# InterfaceGSM.net
KiCad netlist of a schematic drawn in Altium Designer
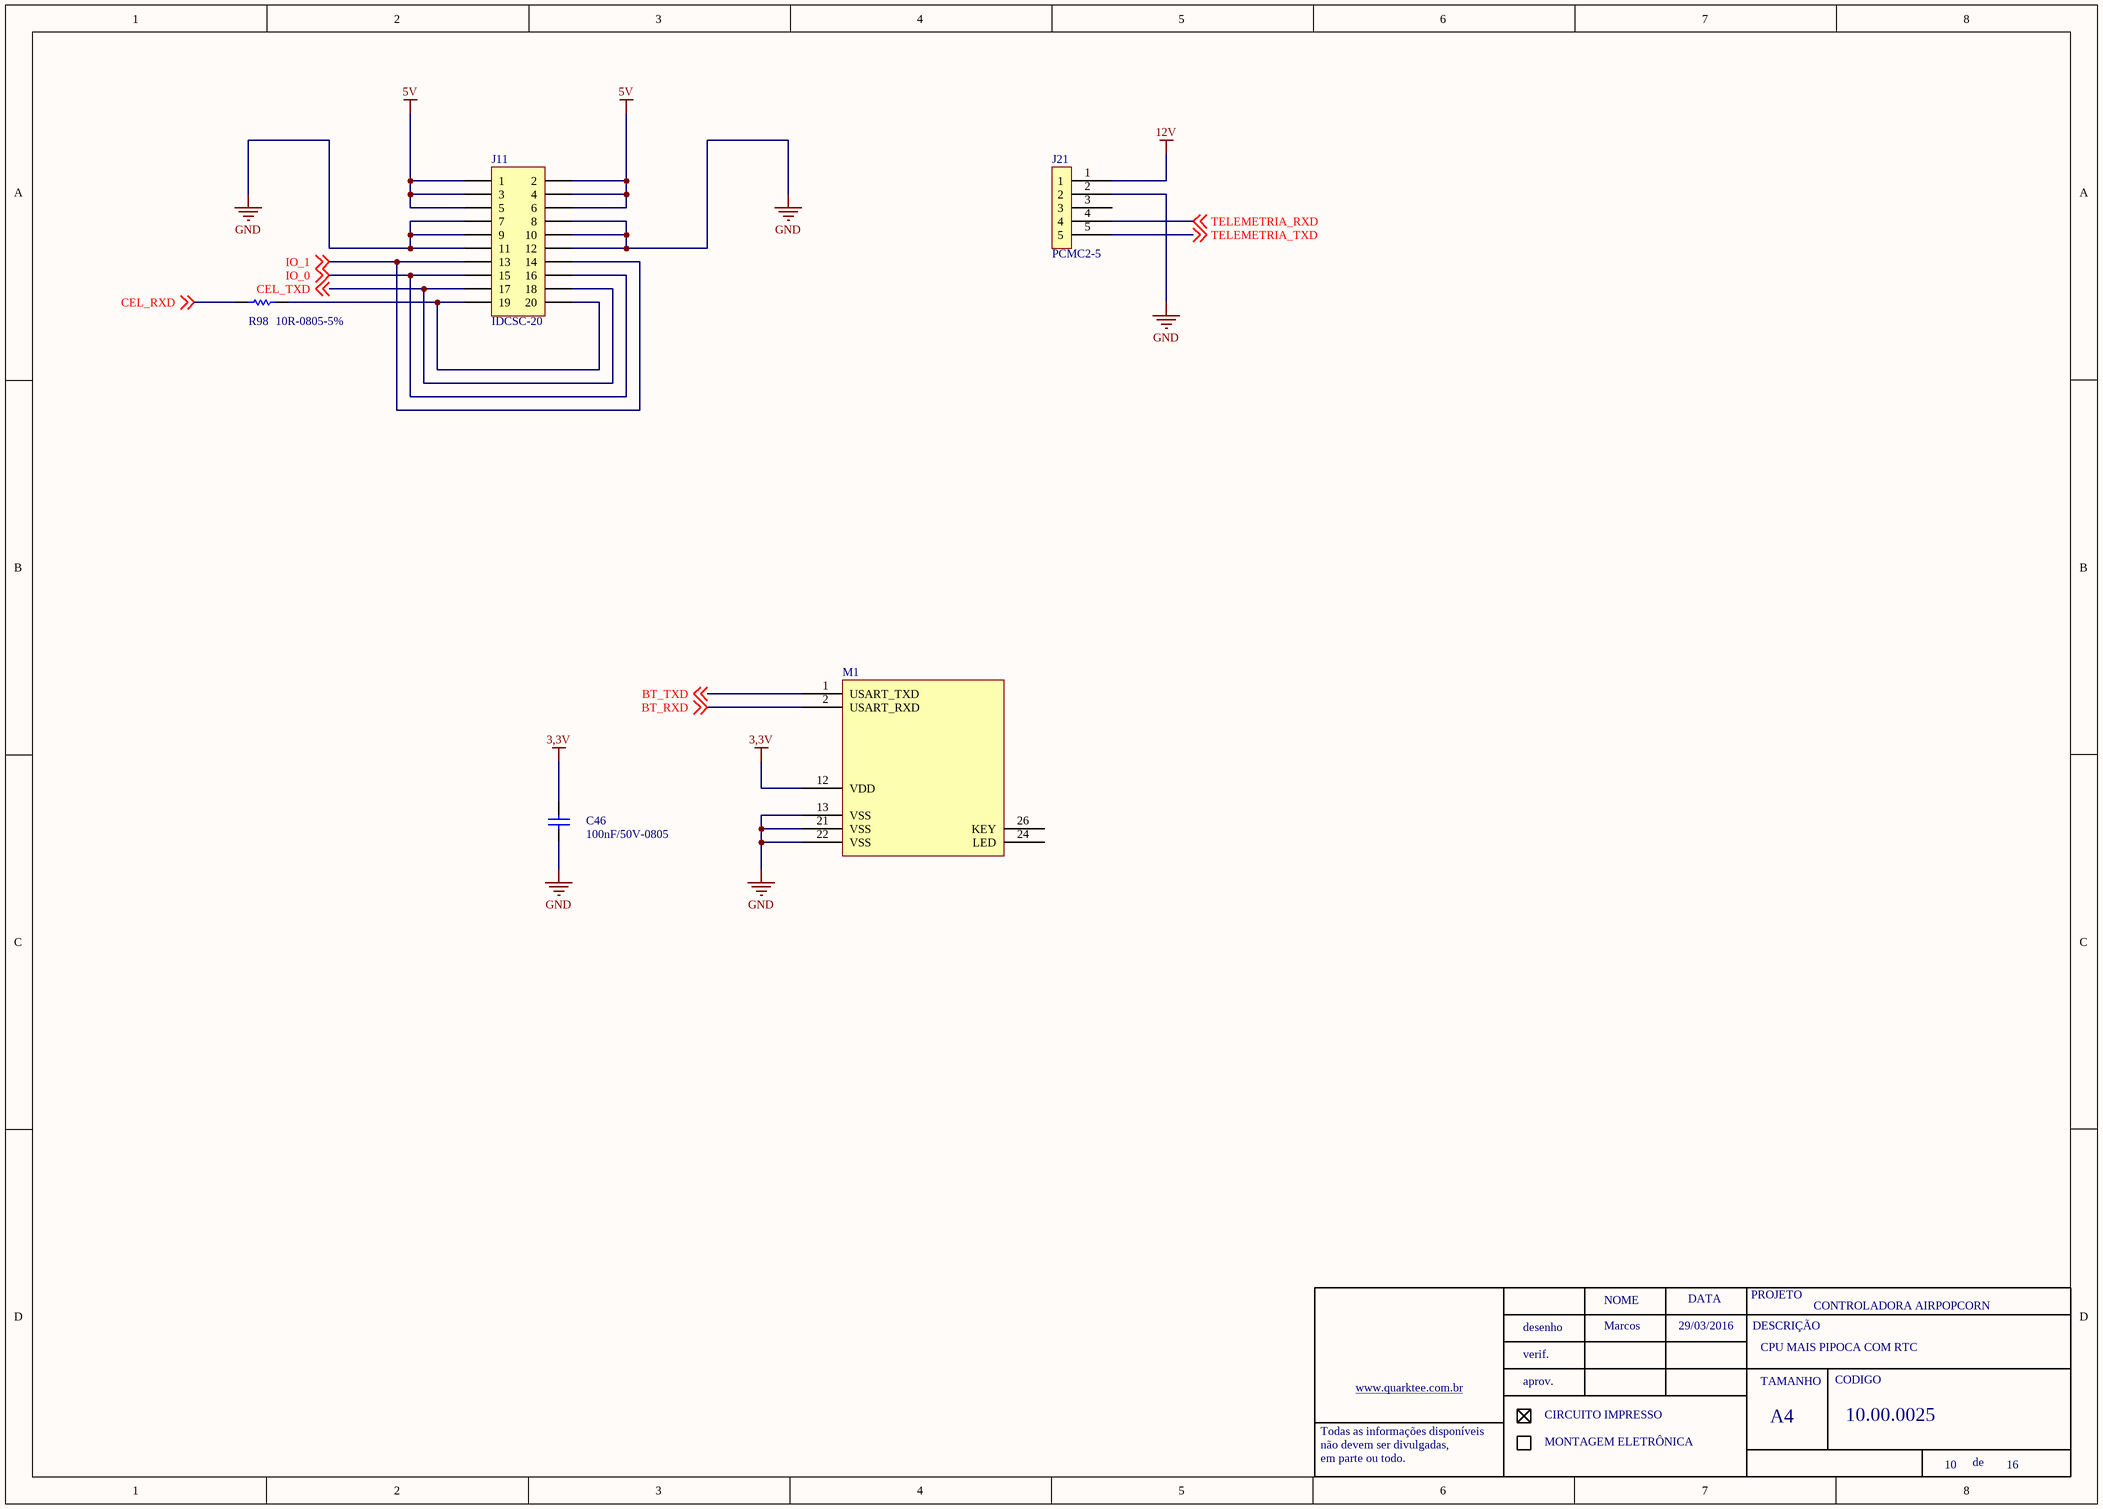
[diagram p0: InterfaceGSM.SchDoc]

(export (version "E")
  (design (tool "Eeschema 10.0.6"))
  (components
    (comp (ref "C46")
      (value "100nF/50V-0805")
      (footprint "0805-REVISADO O")
      (description "100nF/50-0805-NPO")
      (libsource (lib "AquinoLib") (part "100nF/50-0805-NPO"))
    )
    (comp (ref "J11")
      (value "IDCSC-20")
      (footprint "IDCSC-20")
      (libsource (lib "ChaveDigital3") (part "IDC 10x2"))
    )
    (comp (ref "J21") (value "PCMC2-5") (footprint "PCMC2-5") (libsource (lib "AquinoLib") (part "PCMC2-5")))
    (comp (ref "M1") (value "~") (description "HC-06") (libsource (lib "AquinoLib") (part "HC-06 BLUETOOTH")))
    (comp (ref "R98")
      (value "10R-0805-5%")
      (footprint "0805-REVISADO O")
      (libsource (lib "AquinoLib") (part "10R-0805-5%"))
    )
  )
  (nets
    (net (code "1") (name "3,3V") (class "Default")
      (node (ref "C46") (pin "2") (pinfunction "2_2") (pintype "passive"))
      (node (ref "M1") (pin "12") (pinfunction "VDD_12") (pintype "passive"))
    )
    (net (code "2") (name "5V") (class "Default")
      (node (ref "J11") (pin "1") (pinfunction "1_1") (pintype "passive"))
      (node (ref "J11") (pin "2") (pinfunction "2_2") (pintype "passive"))
      (node (ref "J11") (pin "3") (pinfunction "3_3") (pintype "passive"))
      (node (ref "J11") (pin "4") (pinfunction "4_4") (pintype "passive"))
      (node (ref "J11") (pin "5") (pinfunction "5_5") (pintype "passive"))
      (node (ref "J11") (pin "6") (pinfunction "6_6") (pintype "passive"))
    )
    (net (code "3") (name "12V") (class "Default")
      (node (ref "J21") (pin "1") (pinfunction "1_1") (pintype "passive"))
    )
    (net (code "4") (name "BT_RXD") (class "Default")
      (node (ref "M1") (pin "2") (pinfunction "USART_RXD_2") (pintype "passive"))
    )
    (net (code "5") (name "BT_TXD") (class "Default")
      (node (ref "M1") (pin "1") (pinfunction "USART_TXD_1") (pintype "passive"))
    )
    (net (code "6") (name "CEL_RXD") (class "Default")
      (node (ref "R98") (pin "1") (pinfunction "1_1") (pintype "passive"))
    )
    (net (code "7") (name "CEL_TXD") (class "Default")
      (node (ref "J11") (pin "17") (pinfunction "17_17") (pintype "passive"))
      (node (ref "J11") (pin "18") (pinfunction "18_18") (pintype "passive"))
    )
    (net (code "8") (name "GND") (class "Default")
      (node (ref "C46") (pin "1") (pinfunction "1_1") (pintype "passive"))
      (node (ref "J11") (pin "10") (pinfunction "10_10") (pintype "passive"))
      (node (ref "J11") (pin "11") (pinfunction "11_11") (pintype "passive"))
      (node (ref "J11") (pin "12") (pinfunction "12_12") (pintype "passive"))
      (node (ref "J11") (pin "7") (pinfunction "7_7") (pintype "passive"))
      (node (ref "J11") (pin "8") (pinfunction "8_8") (pintype "passive"))
      (node (ref "J11") (pin "9") (pinfunction "9_9") (pintype "passive"))
      (node (ref "J21") (pin "2") (pinfunction "2_2") (pintype "passive"))
      (node (ref "M1") (pin "13") (pinfunction "VSS_13") (pintype "passive"))
      (node (ref "M1") (pin "21") (pinfunction "VSS_21") (pintype "passive"))
      (node (ref "M1") (pin "22") (pinfunction "VSS_22") (pintype "passive"))
    )
    (net (code "9") (name "IO_0") (class "Default")
      (node (ref "J11") (pin "15") (pinfunction "15_15") (pintype "passive"))
      (node (ref "J11") (pin "16") (pinfunction "16_16") (pintype "passive"))
    )
    (net (code "10") (name "IO_1") (class "Default")
      (node (ref "J11") (pin "13") (pinfunction "13_13") (pintype "passive"))
      (node (ref "J11") (pin "14") (pinfunction "14_14") (pintype "passive"))
    )
    (net (code "11") (name "Net-(J11-Pad19)") (class "Default")
      (node (ref "J11") (pin "19") (pinfunction "19_19") (pintype "passive"))
      (node (ref "J11") (pin "20") (pinfunction "20_20") (pintype "passive"))
      (node (ref "R98") (pin "2") (pinfunction "2_2") (pintype "passive"))
    )
    (net (code "12") (name "TELEMETRIA_RXD") (class "Default")
      (node (ref "J21") (pin "4") (pinfunction "4_4") (pintype "passive"))
    )
    (net (code "13") (name "TELEMETRIA_TXD") (class "Default")
      (node (ref "J21") (pin "5") (pinfunction "5_5") (pintype "passive"))
    )
    (net (code "14") (name "unconnected-(J21-Pad3)") (class "Default")
      (node (ref "J21") (pin "3") (pinfunction "3_3") (pintype "passive"))
    )
    (net (code "15") (name "unconnected-(M1-KEY-Pad26)") (class "Default")
      (node (ref "M1") (pin "26") (pinfunction "KEY_26") (pintype "passive"))
    )
    (net (code "16") (name "unconnected-(M1-LED-Pad24)") (class "Default")
      (node (ref "M1") (pin "24") (pinfunction "LED_24") (pintype "passive"))
    )
  )
)
